# untitled.net
KiCad netlist of a schematic drawn in EAGLE
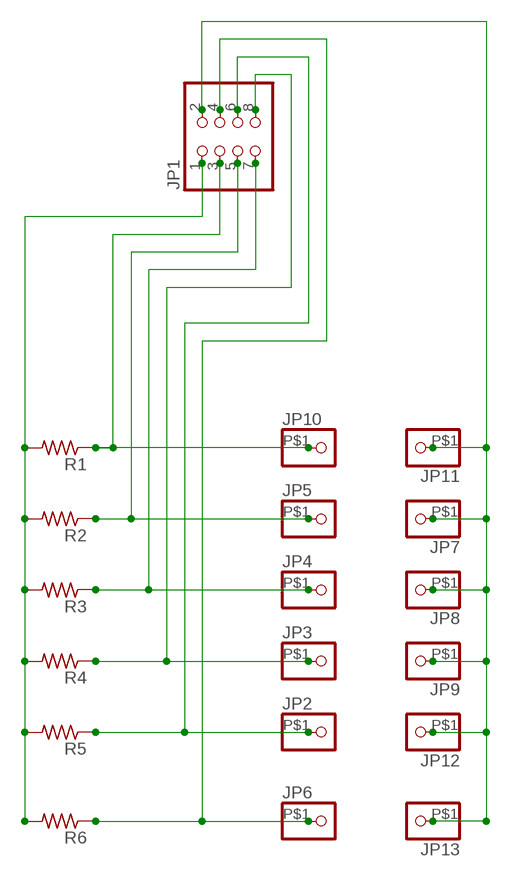
[diagram p0: schematic, sheet 1]

(export (version "E")
  (design (tool "Eeschema 10.0.6"))
  (components
    (comp (ref "JP1")
      (value "PINHD-2X4")
      (footprint "eagle-import:2X04")
      (libsource (lib "eagle-import") (part "PINHD-2X4"))
    )
    (comp (ref "JP2")
      (value "PINHD-1X1-BIGPOGO")
      (footprint "eagle-import:1X1-BIGPOGO")
      (libsource (lib "eagle-import") (part "PINHD-1X1-BIGPOGO"))
    )
    (comp (ref "JP3")
      (value "PINHD-1X1-BIGPOGO")
      (footprint "eagle-import:1X1-BIGPOGO")
      (libsource (lib "eagle-import") (part "PINHD-1X1-BIGPOGO"))
    )
    (comp (ref "JP4")
      (value "PINHD-1X1-BIGPOGO")
      (footprint "eagle-import:1X1-BIGPOGO")
      (libsource (lib "eagle-import") (part "PINHD-1X1-BIGPOGO"))
    )
    (comp (ref "JP5")
      (value "PINHD-1X1-BIGPOGO")
      (footprint "eagle-import:1X1-BIGPOGO")
      (libsource (lib "eagle-import") (part "PINHD-1X1-BIGPOGO"))
    )
    (comp (ref "JP6")
      (value "PINHD-1X1-BIGPOGO")
      (footprint "eagle-import:1X1-BIGPOGO")
      (libsource (lib "eagle-import") (part "PINHD-1X1-BIGPOGO"))
    )
    (comp (ref "JP7")
      (value "PINHD-1X1-BIGPOGO")
      (footprint "eagle-import:1X1-BIGPOGO")
      (libsource (lib "eagle-import") (part "PINHD-1X1-BIGPOGO"))
    )
    (comp (ref "JP8")
      (value "PINHD-1X1-BIGPOGO")
      (footprint "eagle-import:1X1-BIGPOGO")
      (libsource (lib "eagle-import") (part "PINHD-1X1-BIGPOGO"))
    )
    (comp (ref "JP9")
      (value "PINHD-1X1-BIGPOGO")
      (footprint "eagle-import:1X1-BIGPOGO")
      (libsource (lib "eagle-import") (part "PINHD-1X1-BIGPOGO"))
    )
    (comp (ref "JP10")
      (value "PINHD-1X1-BIGPOGO")
      (footprint "eagle-import:1X1-BIGPOGO")
      (libsource (lib "eagle-import") (part "PINHD-1X1-BIGPOGO"))
    )
    (comp (ref "JP11")
      (value "PINHD-1X1-BIGPOGO")
      (footprint "eagle-import:1X1-BIGPOGO")
      (libsource (lib "eagle-import") (part "PINHD-1X1-BIGPOGO"))
    )
    (comp (ref "JP12")
      (value "PINHD-1X1-BIGPOGO")
      (footprint "eagle-import:1X1-BIGPOGO")
      (libsource (lib "eagle-import") (part "PINHD-1X1-BIGPOGO"))
    )
    (comp (ref "JP13")
      (value "PINHD-1X1-BIGPOGO")
      (footprint "eagle-import:1X1-BIGPOGO")
      (libsource (lib "eagle-import") (part "PINHD-1X1-BIGPOGO"))
    )
    (comp (ref "R1")
      (value "R-US_0204/7")
      (footprint "eagle-import:0204_7")
      (libsource (lib "eagle-import") (part "R-US_0204/7"))
    )
    (comp (ref "R2")
      (value "R-US_0204/7")
      (footprint "eagle-import:0204_7")
      (libsource (lib "eagle-import") (part "R-US_0204/7"))
    )
    (comp (ref "R3")
      (value "R-US_0204/7")
      (footprint "eagle-import:0204_7")
      (libsource (lib "eagle-import") (part "R-US_0204/7"))
    )
    (comp (ref "R4")
      (value "R-US_0204/7")
      (footprint "eagle-import:0204_7")
      (libsource (lib "eagle-import") (part "R-US_0204/7"))
    )
    (comp (ref "R5")
      (value "R-US_0204/7")
      (footprint "eagle-import:0204_7")
      (libsource (lib "eagle-import") (part "R-US_0204/7"))
    )
    (comp (ref "R6")
      (value "R-US_0204/7")
      (footprint "eagle-import:0204_7")
      (libsource (lib "eagle-import") (part "R-US_0204/7"))
    )
  )
  (nets
    (net (code "1") (name "Net-(JP1-Pad1)") (class "Default")
      (node (ref "JP1") (pin "1") (pinfunction "1_1") (pintype "passive"))
      (node (ref "R1") (pin "2") (pinfunction "2_2") (pintype "passive"))
      (node (ref "R2") (pin "2") (pinfunction "2_2") (pintype "passive"))
      (node (ref "R3") (pin "2") (pinfunction "2_2") (pintype "passive"))
      (node (ref "R4") (pin "2") (pinfunction "2_2") (pintype "passive"))
      (node (ref "R5") (pin "2") (pinfunction "2_2") (pintype "passive"))
      (node (ref "R6") (pin "2") (pinfunction "2_2") (pintype "passive"))
    )
    (net (code "2") (name "Net-(JP2-1)") (class "Default")
      (node (ref "JP1") (pin "6") (pinfunction "6_6") (pintype "passive"))
      (node (ref "JP2") (pin "P$1") (pinfunction "1_P$1") (pintype "passive"))
      (node (ref "R5") (pin "1") (pinfunction "1_1") (pintype "passive"))
    )
    (net (code "3") (name "Net-(JP3-1)") (class "Default")
      (node (ref "JP1") (pin "8") (pinfunction "8_8") (pintype "passive"))
      (node (ref "JP3") (pin "P$1") (pinfunction "1_P$1") (pintype "passive"))
      (node (ref "R4") (pin "1") (pinfunction "1_1") (pintype "passive"))
    )
    (net (code "4") (name "Net-(JP4-1)") (class "Default")
      (node (ref "JP1") (pin "7") (pinfunction "7_7") (pintype "passive"))
      (node (ref "JP4") (pin "P$1") (pinfunction "1_P$1") (pintype "passive"))
      (node (ref "R3") (pin "1") (pinfunction "1_1") (pintype "passive"))
    )
    (net (code "5") (name "Net-(JP5-1)") (class "Default")
      (node (ref "JP1") (pin "5") (pinfunction "5_5") (pintype "passive"))
      (node (ref "JP5") (pin "P$1") (pinfunction "1_P$1") (pintype "passive"))
      (node (ref "R2") (pin "1") (pinfunction "1_1") (pintype "passive"))
    )
    (net (code "6") (name "Net-(JP6-1)") (class "Default")
      (node (ref "JP1") (pin "4") (pinfunction "4_4") (pintype "passive"))
      (node (ref "JP6") (pin "P$1") (pinfunction "1_P$1") (pintype "passive"))
      (node (ref "R6") (pin "1") (pinfunction "1_1") (pintype "passive"))
    )
    (net (code "7") (name "Net-(JP10-1)") (class "Default")
      (node (ref "JP1") (pin "3") (pinfunction "3_3") (pintype "passive"))
      (node (ref "JP10") (pin "P$1") (pinfunction "1_P$1") (pintype "passive"))
      (node (ref "R1") (pin "1") (pinfunction "1_1") (pintype "passive"))
    )
    (net (code "8") (name "Net-(JP11-1)") (class "Default")
      (node (ref "JP1") (pin "2") (pinfunction "2_2") (pintype "passive"))
      (node (ref "JP11") (pin "P$1") (pinfunction "1_P$1") (pintype "passive"))
      (node (ref "JP12") (pin "P$1") (pinfunction "1_P$1") (pintype "passive"))
      (node (ref "JP13") (pin "P$1") (pinfunction "1_P$1") (pintype "passive"))
      (node (ref "JP7") (pin "P$1") (pinfunction "1_P$1") (pintype "passive"))
      (node (ref "JP8") (pin "P$1") (pinfunction "1_P$1") (pintype "passive"))
      (node (ref "JP9") (pin "P$1") (pinfunction "1_P$1") (pintype "passive"))
    )
  )
)
